# mosfetSwitch.net
KiCad netlist of a schematic drawn in EAGLE
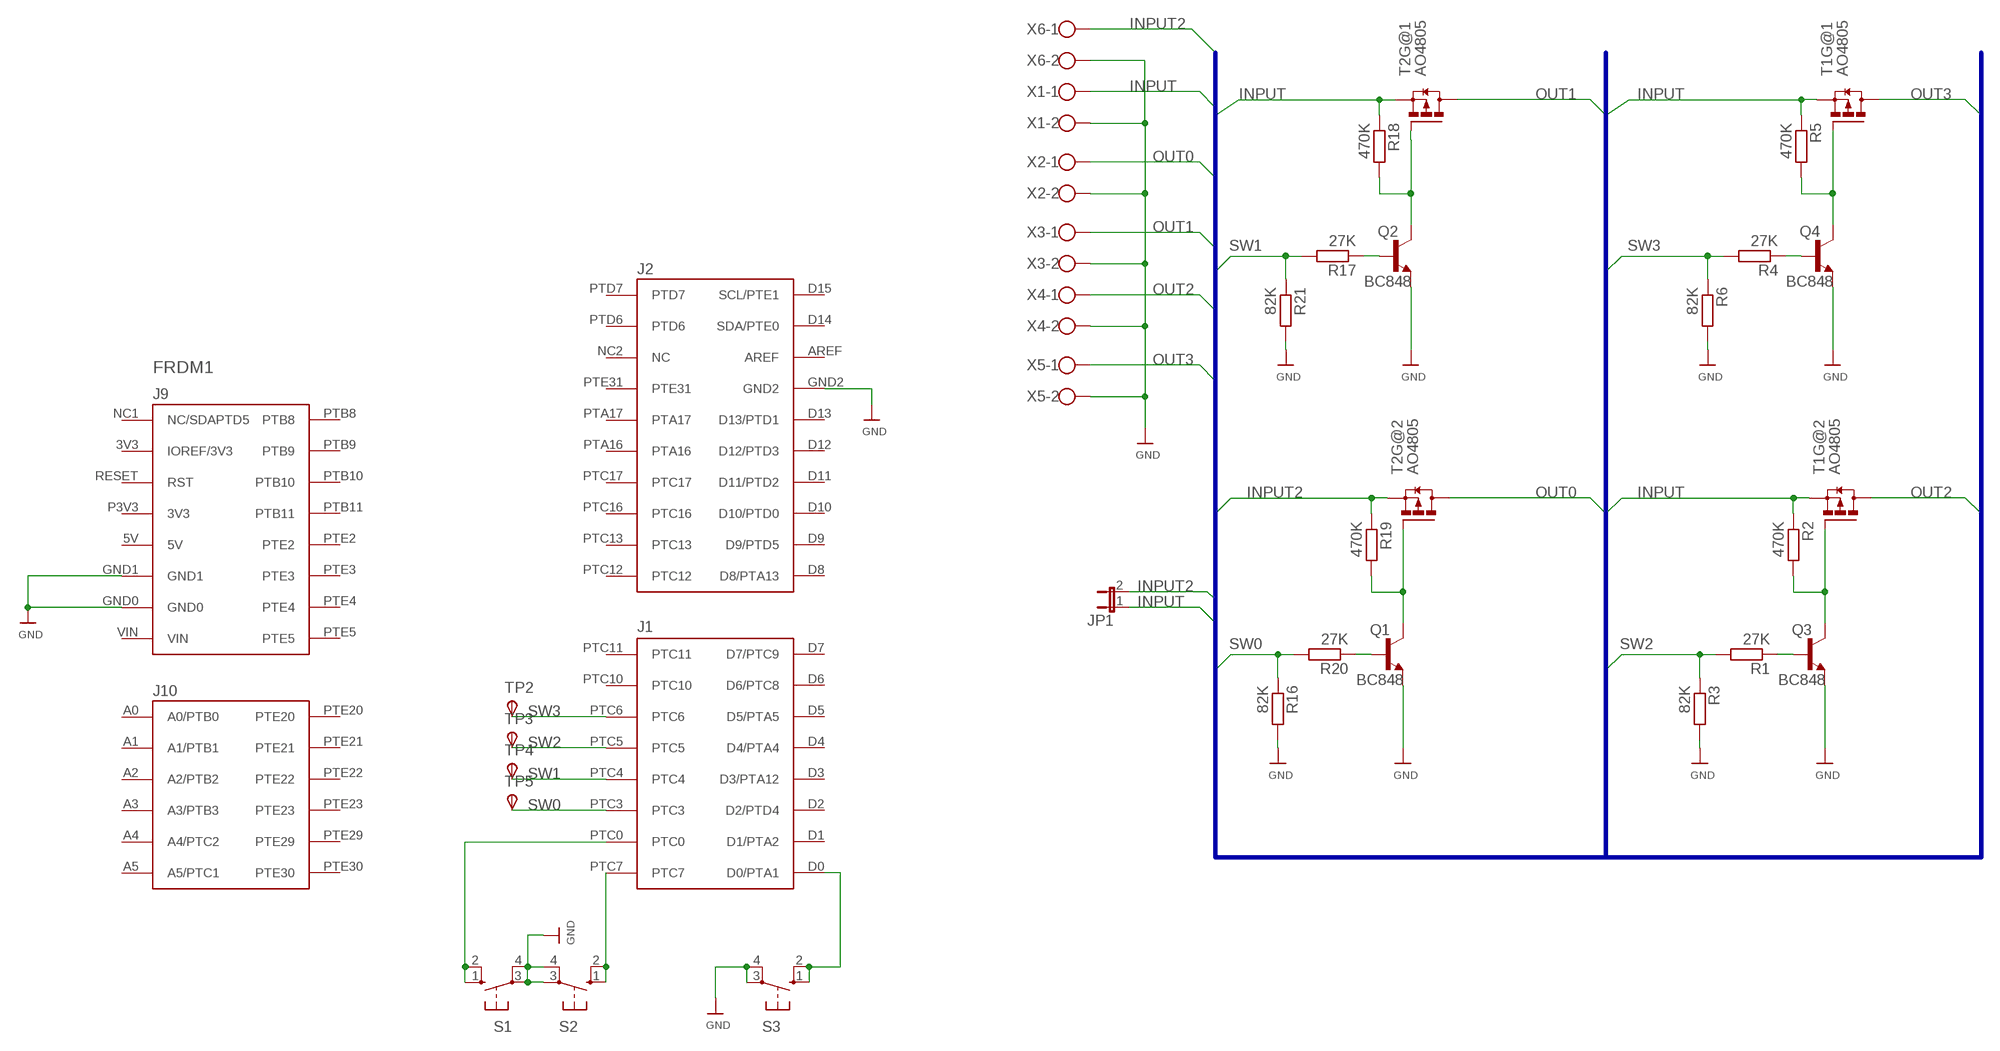
[diagram p0: schematic, sheet 1]

(export (version "E")
  (design (tool "Eeschema 10.0.6"))
  (components
    (comp (ref "FRDM1")
      (value "FRDM-KL25ZNORMAL")
      (footprint "eagle-import:FRDM_KL25Z_NORMAL")
      (libsource (lib "eagle-import") (part "FRDM-KL25ZNORMAL"))
    )
    (comp (ref "JP1")
      (value "JP1E")
      (footprint "eagle-import:JP1")
      (libsource (lib "eagle-import") (part "JP1E"))
    )
    (comp (ref "Q1")
      (value "BC848")
      (footprint "eagle-import:SOT23")
      (libsource (lib "eagle-import") (part "BC848"))
    )
    (comp (ref "Q2")
      (value "BC848")
      (footprint "eagle-import:SOT23")
      (libsource (lib "eagle-import") (part "BC848"))
    )
    (comp (ref "Q3")
      (value "BC848")
      (footprint "eagle-import:SOT23")
      (libsource (lib "eagle-import") (part "BC848"))
    )
    (comp (ref "Q4")
      (value "BC848")
      (footprint "eagle-import:SOT23")
      (libsource (lib "eagle-import") (part "BC848"))
    )
    (comp (ref "R1")
      (value "27K")
      (footprint "eagle-import:R0805")
      (libsource (lib "eagle-import") (part "R-EU_R0805"))
    )
    (comp (ref "R2")
      (value "470K")
      (footprint "eagle-import:R0805")
      (libsource (lib "eagle-import") (part "R-EU_R0805"))
    )
    (comp (ref "R3")
      (value "82K")
      (footprint "eagle-import:R0805")
      (libsource (lib "eagle-import") (part "R-EU_R0805"))
    )
    (comp (ref "R4")
      (value "27K")
      (footprint "eagle-import:R0805")
      (libsource (lib "eagle-import") (part "R-EU_R0805"))
    )
    (comp (ref "R5")
      (value "470K")
      (footprint "eagle-import:R0805")
      (libsource (lib "eagle-import") (part "R-EU_R0805"))
    )
    (comp (ref "R6")
      (value "82K")
      (footprint "eagle-import:R0805")
      (libsource (lib "eagle-import") (part "R-EU_R0805"))
    )
    (comp (ref "R16")
      (value "82K")
      (footprint "eagle-import:R0805")
      (libsource (lib "eagle-import") (part "R-EU_R0805"))
    )
    (comp (ref "R17")
      (value "27K")
      (footprint "eagle-import:R0805")
      (libsource (lib "eagle-import") (part "R-EU_R0805"))
    )
    (comp (ref "R18")
      (value "470K")
      (footprint "eagle-import:R0805")
      (libsource (lib "eagle-import") (part "R-EU_R0805"))
    )
    (comp (ref "R19")
      (value "470K")
      (footprint "eagle-import:R0805")
      (libsource (lib "eagle-import") (part "R-EU_R0805"))
    )
    (comp (ref "R20")
      (value "27K")
      (footprint "eagle-import:R0805")
      (libsource (lib "eagle-import") (part "R-EU_R0805"))
    )
    (comp (ref "R21")
      (value "82K")
      (footprint "eagle-import:R0805")
      (libsource (lib "eagle-import") (part "R-EU_R0805"))
    )
    (comp (ref "S1")
      (value "10-XX3D")
      (footprint "eagle-import:B3F-10XX_2")
      (libsource (lib "eagle-import") (part "10-XX3D"))
    )
    (comp (ref "S2")
      (value "10-XX3D")
      (footprint "eagle-import:B3F-10XX_2")
      (libsource (lib "eagle-import") (part "10-XX3D"))
    )
    (comp (ref "S3")
      (value "10-XX3D")
      (footprint "eagle-import:B3F-10XX_2")
      (libsource (lib "eagle-import") (part "10-XX3D"))
    )
    (comp (ref "T1")
      (value "AO4805")
      (footprint "eagle-import:SOIC127P600X175-8")
      (libsource (lib "eagle-import") (part "AO4805"))
    )
    (comp (ref "T2")
      (value "AO4805")
      (footprint "eagle-import:SOIC127P600X175-8")
      (libsource (lib "eagle-import") (part "AO4805"))
    )
    (comp (ref "TP2")
      (value "TPSB2,54")
      (footprint "eagle-import:B2,54")
      (libsource (lib "eagle-import") (part "TPSB2,54"))
    )
    (comp (ref "TP3")
      (value "TPSB2,54")
      (footprint "eagle-import:B2,54")
      (libsource (lib "eagle-import") (part "TPSB2,54"))
    )
    (comp (ref "TP4")
      (value "TPSB2,54")
      (footprint "eagle-import:B2,54")
      (libsource (lib "eagle-import") (part "TPSB2,54"))
    )
    (comp (ref "TP5")
      (value "TPSB2,54")
      (footprint "eagle-import:B2,54")
      (libsource (lib "eagle-import") (part "TPSB2,54"))
    )
    (comp (ref "X1")
      (value "W237-102")
      (footprint "eagle-import:W237-102")
      (fields (field (name "MPN") "237-102"))
      (libsource (lib "eagle-import") (part "W237-102"))
    )
    (comp (ref "X2")
      (value "W237-102")
      (footprint "eagle-import:W237-102")
      (fields (field (name "MPN") "237-102"))
      (libsource (lib "eagle-import") (part "W237-102"))
    )
    (comp (ref "X3")
      (value "W237-102")
      (footprint "eagle-import:W237-102")
      (fields (field (name "MPN") "237-102"))
      (libsource (lib "eagle-import") (part "W237-102"))
    )
    (comp (ref "X4")
      (value "W237-102")
      (footprint "eagle-import:W237-102")
      (fields (field (name "MPN") "237-102"))
      (libsource (lib "eagle-import") (part "W237-102"))
    )
    (comp (ref "X5")
      (value "W237-102")
      (footprint "eagle-import:W237-102")
      (fields (field (name "MPN") "237-102"))
      (libsource (lib "eagle-import") (part "W237-102"))
    )
    (comp (ref "X6")
      (value "W237-102")
      (footprint "eagle-import:W237-102")
      (fields (field (name "MPN") "237-102"))
      (libsource (lib "eagle-import") (part "W237-102"))
    )
  )
  (nets
    (net (code "1") (name "/INPUT") (class "Default")
      (node (ref "JP1") (pin "1") (pinfunction "1_1") (pintype "passive"))
      (node (ref "R18") (pin "1") (pinfunction "1_1") (pintype "passive"))
      (node (ref "R2") (pin "1") (pinfunction "1_1") (pintype "passive"))
      (node (ref "R5") (pin "1") (pinfunction "1_1") (pintype "passive"))
      (node (ref "T1") (pin "1") (pinfunction "S_1") (pintype "passive"))
      (node (ref "T1") (pin "3") (pinfunction "S_3") (pintype "passive"))
      (node (ref "T2") (pin "3") (pinfunction "S_3") (pintype "passive"))
      (node (ref "X1") (pin "1") (pinfunction "KL_1") (pintype "passive"))
    )
    (net (code "2") (name "/INPUT2") (class "Default")
      (node (ref "JP1") (pin "2") (pinfunction "2_2") (pintype "passive"))
      (node (ref "R19") (pin "1") (pinfunction "1_1") (pintype "passive"))
      (node (ref "T2") (pin "1") (pinfunction "S_1") (pintype "passive"))
      (node (ref "X6") (pin "1") (pinfunction "KL_1") (pintype "passive"))
    )
    (net (code "3") (name "/OUT0") (class "Default")
      (node (ref "T2") (pin "7") (pinfunction "D_7") (pintype "passive"))
      (node (ref "T2") (pin "8") (pinfunction "D_8") (pintype "passive"))
      (node (ref "X2") (pin "1") (pinfunction "KL_1") (pintype "passive"))
    )
    (net (code "4") (name "/OUT1") (class "Default")
      (node (ref "T2") (pin "5") (pinfunction "D_5") (pintype "passive"))
      (node (ref "T2") (pin "6") (pinfunction "D_6") (pintype "passive"))
      (node (ref "X3") (pin "1") (pinfunction "KL_1") (pintype "passive"))
    )
    (net (code "5") (name "/OUT2") (class "Default")
      (node (ref "T1") (pin "7") (pinfunction "D_7") (pintype "passive"))
      (node (ref "T1") (pin "8") (pinfunction "D_8") (pintype "passive"))
      (node (ref "X4") (pin "1") (pinfunction "KL_1") (pintype "passive"))
    )
    (net (code "6") (name "/OUT3") (class "Default")
      (node (ref "T1") (pin "5") (pinfunction "D_5") (pintype "passive"))
      (node (ref "T1") (pin "6") (pinfunction "D_6") (pintype "passive"))
      (node (ref "X5") (pin "1") (pinfunction "KL_1") (pintype "passive"))
    )
    (net (code "7") (name "/SW0") (class "Default")
      (node (ref "FRDM1") (pin "PTC3") (pinfunction "PTC3_PTC3") (pintype "bidirectional"))
      (node (ref "R16") (pin "1") (pinfunction "1_1") (pintype "passive"))
      (node (ref "R20") (pin "2") (pinfunction "2_2") (pintype "passive"))
      (node (ref "TP5") (pin "TP") (pinfunction "PP_TP") (pintype "input"))
    )
    (net (code "8") (name "/SW1") (class "Default")
      (node (ref "FRDM1") (pin "PTC4") (pinfunction "PTC4_PTC4") (pintype "bidirectional"))
      (node (ref "R17") (pin "2") (pinfunction "2_2") (pintype "passive"))
      (node (ref "R21") (pin "1") (pinfunction "1_1") (pintype "passive"))
      (node (ref "TP4") (pin "TP") (pinfunction "PP_TP") (pintype "input"))
    )
    (net (code "9") (name "/SW2") (class "Default")
      (node (ref "FRDM1") (pin "PTC5") (pinfunction "PTC5_PTC5") (pintype "bidirectional"))
      (node (ref "R1") (pin "2") (pinfunction "2_2") (pintype "passive"))
      (node (ref "R3") (pin "1") (pinfunction "1_1") (pintype "passive"))
      (node (ref "TP3") (pin "TP") (pinfunction "PP_TP") (pintype "input"))
    )
    (net (code "10") (name "/SW3") (class "Default")
      (node (ref "FRDM1") (pin "PTC6") (pinfunction "PTC6_PTC6") (pintype "bidirectional"))
      (node (ref "R4") (pin "2") (pinfunction "2_2") (pintype "passive"))
      (node (ref "R6") (pin "1") (pinfunction "1_1") (pintype "passive"))
      (node (ref "TP2") (pin "TP") (pinfunction "PP_TP") (pintype "input"))
    )
    (net (code "11") (name "GND") (class "Default")
      (node (ref "FRDM1") (pin "GND0") (pinfunction "GND0_GND0") (pintype "bidirectional"))
      (node (ref "FRDM1") (pin "GND1") (pinfunction "GND1_GND1") (pintype "bidirectional"))
      (node (ref "FRDM1") (pin "GND2") (pinfunction "GND2_GND2") (pintype "bidirectional"))
      (node (ref "Q1") (pin "2") (pinfunction "E_2") (pintype "passive"))
      (node (ref "Q2") (pin "2") (pinfunction "E_2") (pintype "passive"))
      (node (ref "Q3") (pin "2") (pinfunction "E_2") (pintype "passive"))
      (node (ref "Q4") (pin "2") (pinfunction "E_2") (pintype "passive"))
      (node (ref "R16") (pin "2") (pinfunction "2_2") (pintype "passive"))
      (node (ref "R21") (pin "2") (pinfunction "2_2") (pintype "passive"))
      (node (ref "R3") (pin "2") (pinfunction "2_2") (pintype "passive"))
      (node (ref "R6") (pin "2") (pinfunction "2_2") (pintype "passive"))
      (node (ref "S1") (pin "3") (pinfunction "P_3") (pintype "passive"))
      (node (ref "S1") (pin "4") (pinfunction "P1_4") (pintype "passive"))
      (node (ref "S2") (pin "3") (pinfunction "P_3") (pintype "passive"))
      (node (ref "S2") (pin "4") (pinfunction "P1_4") (pintype "passive"))
      (node (ref "S3") (pin "3") (pinfunction "P_3") (pintype "passive"))
      (node (ref "S3") (pin "4") (pinfunction "P1_4") (pintype "passive"))
      (node (ref "X1") (pin "2") (pinfunction "KL_2") (pintype "passive"))
      (node (ref "X2") (pin "2") (pinfunction "KL_2") (pintype "passive"))
      (node (ref "X3") (pin "2") (pinfunction "KL_2") (pintype "passive"))
      (node (ref "X4") (pin "2") (pinfunction "KL_2") (pintype "passive"))
      (node (ref "X5") (pin "2") (pinfunction "KL_2") (pintype "passive"))
      (node (ref "X6") (pin "2") (pinfunction "KL_2") (pintype "passive"))
    )
    (net (code "12") (name "Net-(FRDM1-D0{slash}PTA1)") (class "Default")
      (node (ref "FRDM1") (pin "D0") (pinfunction "D0/PTA1_D0") (pintype "bidirectional"))
      (node (ref "S3") (pin "1") (pinfunction "S_1") (pintype "passive"))
      (node (ref "S3") (pin "2") (pinfunction "S1_2") (pintype "passive"))
    )
    (net (code "13") (name "Net-(Q1-B)") (class "Default")
      (node (ref "Q1") (pin "1") (pinfunction "B_1") (pintype "passive"))
      (node (ref "R20") (pin "1") (pinfunction "1_1") (pintype "passive"))
    )
    (net (code "14") (name "Net-(Q1-C)") (class "Default")
      (node (ref "Q1") (pin "3") (pinfunction "C_3") (pintype "passive"))
      (node (ref "R19") (pin "2") (pinfunction "2_2") (pintype "passive"))
      (node (ref "T2") (pin "2") (pinfunction "G_2") (pintype "passive"))
    )
    (net (code "15") (name "Net-(Q2-B)") (class "Default")
      (node (ref "Q2") (pin "1") (pinfunction "B_1") (pintype "passive"))
      (node (ref "R17") (pin "1") (pinfunction "1_1") (pintype "passive"))
    )
    (net (code "16") (name "Net-(Q2-C)") (class "Default")
      (node (ref "Q2") (pin "3") (pinfunction "C_3") (pintype "passive"))
      (node (ref "R18") (pin "2") (pinfunction "2_2") (pintype "passive"))
      (node (ref "T2") (pin "4") (pinfunction "G_4") (pintype "passive"))
    )
    (net (code "17") (name "Net-(Q3-B)") (class "Default")
      (node (ref "Q3") (pin "1") (pinfunction "B_1") (pintype "passive"))
      (node (ref "R1") (pin "1") (pinfunction "1_1") (pintype "passive"))
    )
    (net (code "18") (name "Net-(Q3-C)") (class "Default")
      (node (ref "Q3") (pin "3") (pinfunction "C_3") (pintype "passive"))
      (node (ref "R2") (pin "2") (pinfunction "2_2") (pintype "passive"))
      (node (ref "T1") (pin "2") (pinfunction "G_2") (pintype "passive"))
    )
    (net (code "19") (name "Net-(Q4-B)") (class "Default")
      (node (ref "Q4") (pin "1") (pinfunction "B_1") (pintype "passive"))
      (node (ref "R4") (pin "1") (pinfunction "1_1") (pintype "passive"))
    )
    (net (code "20") (name "Net-(Q4-C)") (class "Default")
      (node (ref "Q4") (pin "3") (pinfunction "C_3") (pintype "passive"))
      (node (ref "R5") (pin "2") (pinfunction "2_2") (pintype "passive"))
      (node (ref "T1") (pin "4") (pinfunction "G_4") (pintype "passive"))
    )
    (net (code "21") (name "Net-(S1-S)") (class "Default")
      (node (ref "FRDM1") (pin "PTC0") (pinfunction "PTC0_PTC0") (pintype "bidirectional"))
      (node (ref "S1") (pin "1") (pinfunction "S_1") (pintype "passive"))
      (node (ref "S1") (pin "2") (pinfunction "S1_2") (pintype "passive"))
    )
    (net (code "22") (name "Net-(S2-S)") (class "Default")
      (node (ref "FRDM1") (pin "PTC7") (pinfunction "PTC7_PTC7") (pintype "bidirectional"))
      (node (ref "S2") (pin "1") (pinfunction "S_1") (pintype "passive"))
      (node (ref "S2") (pin "2") (pinfunction "S1_2") (pintype "passive"))
    )
    (net (code "23") (name "unconnected-(FRDM1-3V3-PadP3V3)") (class "Default")
      (node (ref "FRDM1") (pin "P3V3") (pinfunction "3V3_P3V3") (pintype "bidirectional"))
    )
    (net (code "24") (name "unconnected-(FRDM1-A0{slash}PTB0-PadA0)") (class "Default")
      (node (ref "FRDM1") (pin "A0") (pinfunction "A0/PTB0_A0") (pintype "bidirectional"))
    )
    (net (code "25") (name "unconnected-(FRDM1-A1{slash}PTB1-PadA1)") (class "Default")
      (node (ref "FRDM1") (pin "A1") (pinfunction "A1/PTB1_A1") (pintype "bidirectional"))
    )
    (net (code "26") (name "unconnected-(FRDM1-A2{slash}PTB2-PadA2)") (class "Default")
      (node (ref "FRDM1") (pin "A2") (pinfunction "A2/PTB2_A2") (pintype "bidirectional"))
    )
    (net (code "27") (name "unconnected-(FRDM1-A3{slash}PTB3-PadA3)") (class "Default")
      (node (ref "FRDM1") (pin "A3") (pinfunction "A3/PTB3_A3") (pintype "bidirectional"))
    )
    (net (code "28") (name "unconnected-(FRDM1-A4{slash}PTC2-PadA4)") (class "Default")
      (node (ref "FRDM1") (pin "A4") (pinfunction "A4/PTC2_A4") (pintype "bidirectional"))
    )
    (net (code "29") (name "unconnected-(FRDM1-A5{slash}PTC1-PadA5)") (class "Default")
      (node (ref "FRDM1") (pin "A5") (pinfunction "A5/PTC1_A5") (pintype "bidirectional"))
    )
    (net (code "30") (name "unconnected-(FRDM1-D1{slash}PTA2-PadD1)") (class "Default")
      (node (ref "FRDM1") (pin "D1") (pinfunction "D1/PTA2_D1") (pintype "bidirectional"))
    )
    (net (code "31") (name "unconnected-(FRDM1-D2{slash}PTD4-PadD2)") (class "Default")
      (node (ref "FRDM1") (pin "D2") (pinfunction "D2/PTD4_D2") (pintype "bidirectional"))
    )
    (net (code "32") (name "unconnected-(FRDM1-D3{slash}PTA12-PadD3)") (class "Default")
      (node (ref "FRDM1") (pin "D3") (pinfunction "D3/PTA12_D3") (pintype "bidirectional"))
    )
    (net (code "33") (name "unconnected-(FRDM1-D4{slash}PTA4-PadD4)") (class "Default")
      (node (ref "FRDM1") (pin "D4") (pinfunction "D4/PTA4_D4") (pintype "bidirectional"))
    )
    (net (code "34") (name "unconnected-(FRDM1-D5{slash}PTA5-PadD5)") (class "Default")
      (node (ref "FRDM1") (pin "D5") (pinfunction "D5/PTA5_D5") (pintype "bidirectional"))
    )
    (net (code "35") (name "unconnected-(FRDM1-D6{slash}PTC8-PadD6)") (class "Default")
      (node (ref "FRDM1") (pin "D6") (pinfunction "D6/PTC8_D6") (pintype "bidirectional"))
    )
    (net (code "36") (name "unconnected-(FRDM1-D7{slash}PTC9-PadD7)") (class "Default")
      (node (ref "FRDM1") (pin "D7") (pinfunction "D7/PTC9_D7") (pintype "bidirectional"))
    )
    (net (code "37") (name "unconnected-(FRDM1-D8{slash}PTA13-PadD8)") (class "Default")
      (node (ref "FRDM1") (pin "D8") (pinfunction "D8/PTA13_D8") (pintype "bidirectional"))
    )
    (net (code "38") (name "unconnected-(FRDM1-D9{slash}PTD5-PadD9)") (class "Default")
      (node (ref "FRDM1") (pin "D9") (pinfunction "D9/PTD5_D9") (pintype "bidirectional"))
    )
    (net (code "39") (name "unconnected-(FRDM1-D10{slash}PTD0-PadD10)") (class "Default")
      (node (ref "FRDM1") (pin "D10") (pinfunction "D10/PTD0_D10") (pintype "bidirectional"))
    )
    (net (code "40") (name "unconnected-(FRDM1-D11{slash}PTD2-PadD11)") (class "Default")
      (node (ref "FRDM1") (pin "D11") (pinfunction "D11/PTD2_D11") (pintype "bidirectional"))
    )
    (net (code "41") (name "unconnected-(FRDM1-D12{slash}PTD3-PadD12)") (class "Default")
      (node (ref "FRDM1") (pin "D12") (pinfunction "D12/PTD3_D12") (pintype "bidirectional"))
    )
    (net (code "42") (name "unconnected-(FRDM1-D13{slash}PTD1-PadD13)") (class "Default")
      (node (ref "FRDM1") (pin "D13") (pinfunction "D13/PTD1_D13") (pintype "bidirectional"))
    )
    (net (code "43") (name "unconnected-(FRDM1-IOREF{slash}3V3-Pad3V3)") (class "Default")
      (node (ref "FRDM1") (pin "3V3") (pinfunction "IOREF/3V3_3V3") (pintype "bidirectional"))
    )
    (net (code "44") (name "unconnected-(FRDM1-NC-PadNC2)") (class "Default")
      (node (ref "FRDM1") (pin "NC2") (pinfunction "NC_NC2") (pintype "bidirectional"))
    )
    (net (code "45") (name "unconnected-(FRDM1-NC{slash}SDAPTD5-PadNC1)") (class "Default")
      (node (ref "FRDM1") (pin "NC1") (pinfunction "NC/SDAPTD5_NC1") (pintype "bidirectional"))
    )
    (net (code "46") (name "unconnected-(FRDM1-Pad5V)") (class "Default")
      (node (ref "FRDM1") (pin "5V") (pinfunction "5V_5V") (pintype "bidirectional"))
    )
    (net (code "47") (name "unconnected-(FRDM1-PadAREF)") (class "Default")
      (node (ref "FRDM1") (pin "AREF") (pinfunction "AREF_AREF") (pintype "bidirectional"))
    )
    (net (code "48") (name "unconnected-(FRDM1-PadPTA16)") (class "Default")
      (node (ref "FRDM1") (pin "PTA16") (pinfunction "PTA16_PTA16") (pintype "bidirectional"))
    )
    (net (code "49") (name "unconnected-(FRDM1-PadPTA17)") (class "Default")
      (node (ref "FRDM1") (pin "PTA17") (pinfunction "PTA17_PTA17") (pintype "bidirectional"))
    )
    (net (code "50") (name "unconnected-(FRDM1-PadPTB8)") (class "Default")
      (node (ref "FRDM1") (pin "PTB8") (pinfunction "PTB8_PTB8") (pintype "bidirectional"))
    )
    (net (code "51") (name "unconnected-(FRDM1-PadPTB9)") (class "Default")
      (node (ref "FRDM1") (pin "PTB9") (pinfunction "PTB9_PTB9") (pintype "bidirectional"))
    )
    (net (code "52") (name "unconnected-(FRDM1-PadPTB10)") (class "Default")
      (node (ref "FRDM1") (pin "PTB10") (pinfunction "PTB10_PTB10") (pintype "bidirectional"))
    )
    (net (code "53") (name "unconnected-(FRDM1-PadPTB11)") (class "Default")
      (node (ref "FRDM1") (pin "PTB11") (pinfunction "PTB11_PTB11") (pintype "bidirectional"))
    )
    (net (code "54") (name "unconnected-(FRDM1-PadPTC10)") (class "Default")
      (node (ref "FRDM1") (pin "PTC10") (pinfunction "PTC10_PTC10") (pintype "bidirectional"))
    )
    (net (code "55") (name "unconnected-(FRDM1-PadPTC11)") (class "Default")
      (node (ref "FRDM1") (pin "PTC11") (pinfunction "PTC11_PTC11") (pintype "bidirectional"))
    )
    (net (code "56") (name "unconnected-(FRDM1-PadPTC12)") (class "Default")
      (node (ref "FRDM1") (pin "PTC12") (pinfunction "PTC12_PTC12") (pintype "bidirectional"))
    )
    (net (code "57") (name "unconnected-(FRDM1-PadPTC13)") (class "Default")
      (node (ref "FRDM1") (pin "PTC13") (pinfunction "PTC13_PTC13") (pintype "bidirectional"))
    )
    (net (code "58") (name "unconnected-(FRDM1-PadPTC16)") (class "Default")
      (node (ref "FRDM1") (pin "PTC16") (pinfunction "PTC16_PTC16") (pintype "bidirectional"))
    )
    (net (code "59") (name "unconnected-(FRDM1-PadPTC17)") (class "Default")
      (node (ref "FRDM1") (pin "PTC17") (pinfunction "PTC17_PTC17") (pintype "bidirectional"))
    )
    (net (code "60") (name "unconnected-(FRDM1-PadPTD6)") (class "Default")
      (node (ref "FRDM1") (pin "PTD6") (pinfunction "PTD6_PTD6") (pintype "bidirectional"))
    )
    (net (code "61") (name "unconnected-(FRDM1-PadPTD7)") (class "Default")
      (node (ref "FRDM1") (pin "PTD7") (pinfunction "PTD7_PTD7") (pintype "bidirectional"))
    )
    (net (code "62") (name "unconnected-(FRDM1-PadPTE2)") (class "Default")
      (node (ref "FRDM1") (pin "PTE2") (pinfunction "PTE2_PTE2") (pintype "bidirectional"))
    )
    (net (code "63") (name "unconnected-(FRDM1-PadPTE3)") (class "Default")
      (node (ref "FRDM1") (pin "PTE3") (pinfunction "PTE3_PTE3") (pintype "bidirectional"))
    )
    (net (code "64") (name "unconnected-(FRDM1-PadPTE4)") (class "Default")
      (node (ref "FRDM1") (pin "PTE4") (pinfunction "PTE4_PTE4") (pintype "bidirectional"))
    )
    (net (code "65") (name "unconnected-(FRDM1-PadPTE5)") (class "Default")
      (node (ref "FRDM1") (pin "PTE5") (pinfunction "PTE5_PTE5") (pintype "bidirectional"))
    )
    (net (code "66") (name "unconnected-(FRDM1-PadPTE20)") (class "Default")
      (node (ref "FRDM1") (pin "PTE20") (pinfunction "PTE20_PTE20") (pintype "bidirectional"))
    )
    (net (code "67") (name "unconnected-(FRDM1-PadPTE21)") (class "Default")
      (node (ref "FRDM1") (pin "PTE21") (pinfunction "PTE21_PTE21") (pintype "bidirectional"))
    )
    (net (code "68") (name "unconnected-(FRDM1-PadPTE22)") (class "Default")
      (node (ref "FRDM1") (pin "PTE22") (pinfunction "PTE22_PTE22") (pintype "bidirectional"))
    )
    (net (code "69") (name "unconnected-(FRDM1-PadPTE23)") (class "Default")
      (node (ref "FRDM1") (pin "PTE23") (pinfunction "PTE23_PTE23") (pintype "bidirectional"))
    )
    (net (code "70") (name "unconnected-(FRDM1-PadPTE29)") (class "Default")
      (node (ref "FRDM1") (pin "PTE29") (pinfunction "PTE29_PTE29") (pintype "bidirectional"))
    )
    (net (code "71") (name "unconnected-(FRDM1-PadPTE30)") (class "Default")
      (node (ref "FRDM1") (pin "PTE30") (pinfunction "PTE30_PTE30") (pintype "bidirectional"))
    )
    (net (code "72") (name "unconnected-(FRDM1-PadPTE31)") (class "Default")
      (node (ref "FRDM1") (pin "PTE31") (pinfunction "PTE31_PTE31") (pintype "bidirectional"))
    )
    (net (code "73") (name "unconnected-(FRDM1-PadVIN)") (class "Default")
      (node (ref "FRDM1") (pin "VIN") (pinfunction "VIN_VIN") (pintype "bidirectional"))
    )
    (net (code "74") (name "unconnected-(FRDM1-RST-PadRESET)") (class "Default")
      (node (ref "FRDM1") (pin "RESET") (pinfunction "RST_RESET") (pintype "bidirectional"))
    )
    (net (code "75") (name "unconnected-(FRDM1-SCL{slash}PTE1-PadD15)") (class "Default")
      (node (ref "FRDM1") (pin "D15") (pinfunction "SCL/PTE1_D15") (pintype "bidirectional"))
    )
    (net (code "76") (name "unconnected-(FRDM1-SDA{slash}PTE0-PadD14)") (class "Default")
      (node (ref "FRDM1") (pin "D14") (pinfunction "SDA/PTE0_D14") (pintype "bidirectional"))
    )
  )
)
